# familab_pov_finished.net
KiCad netlist of a schematic drawn in EAGLE
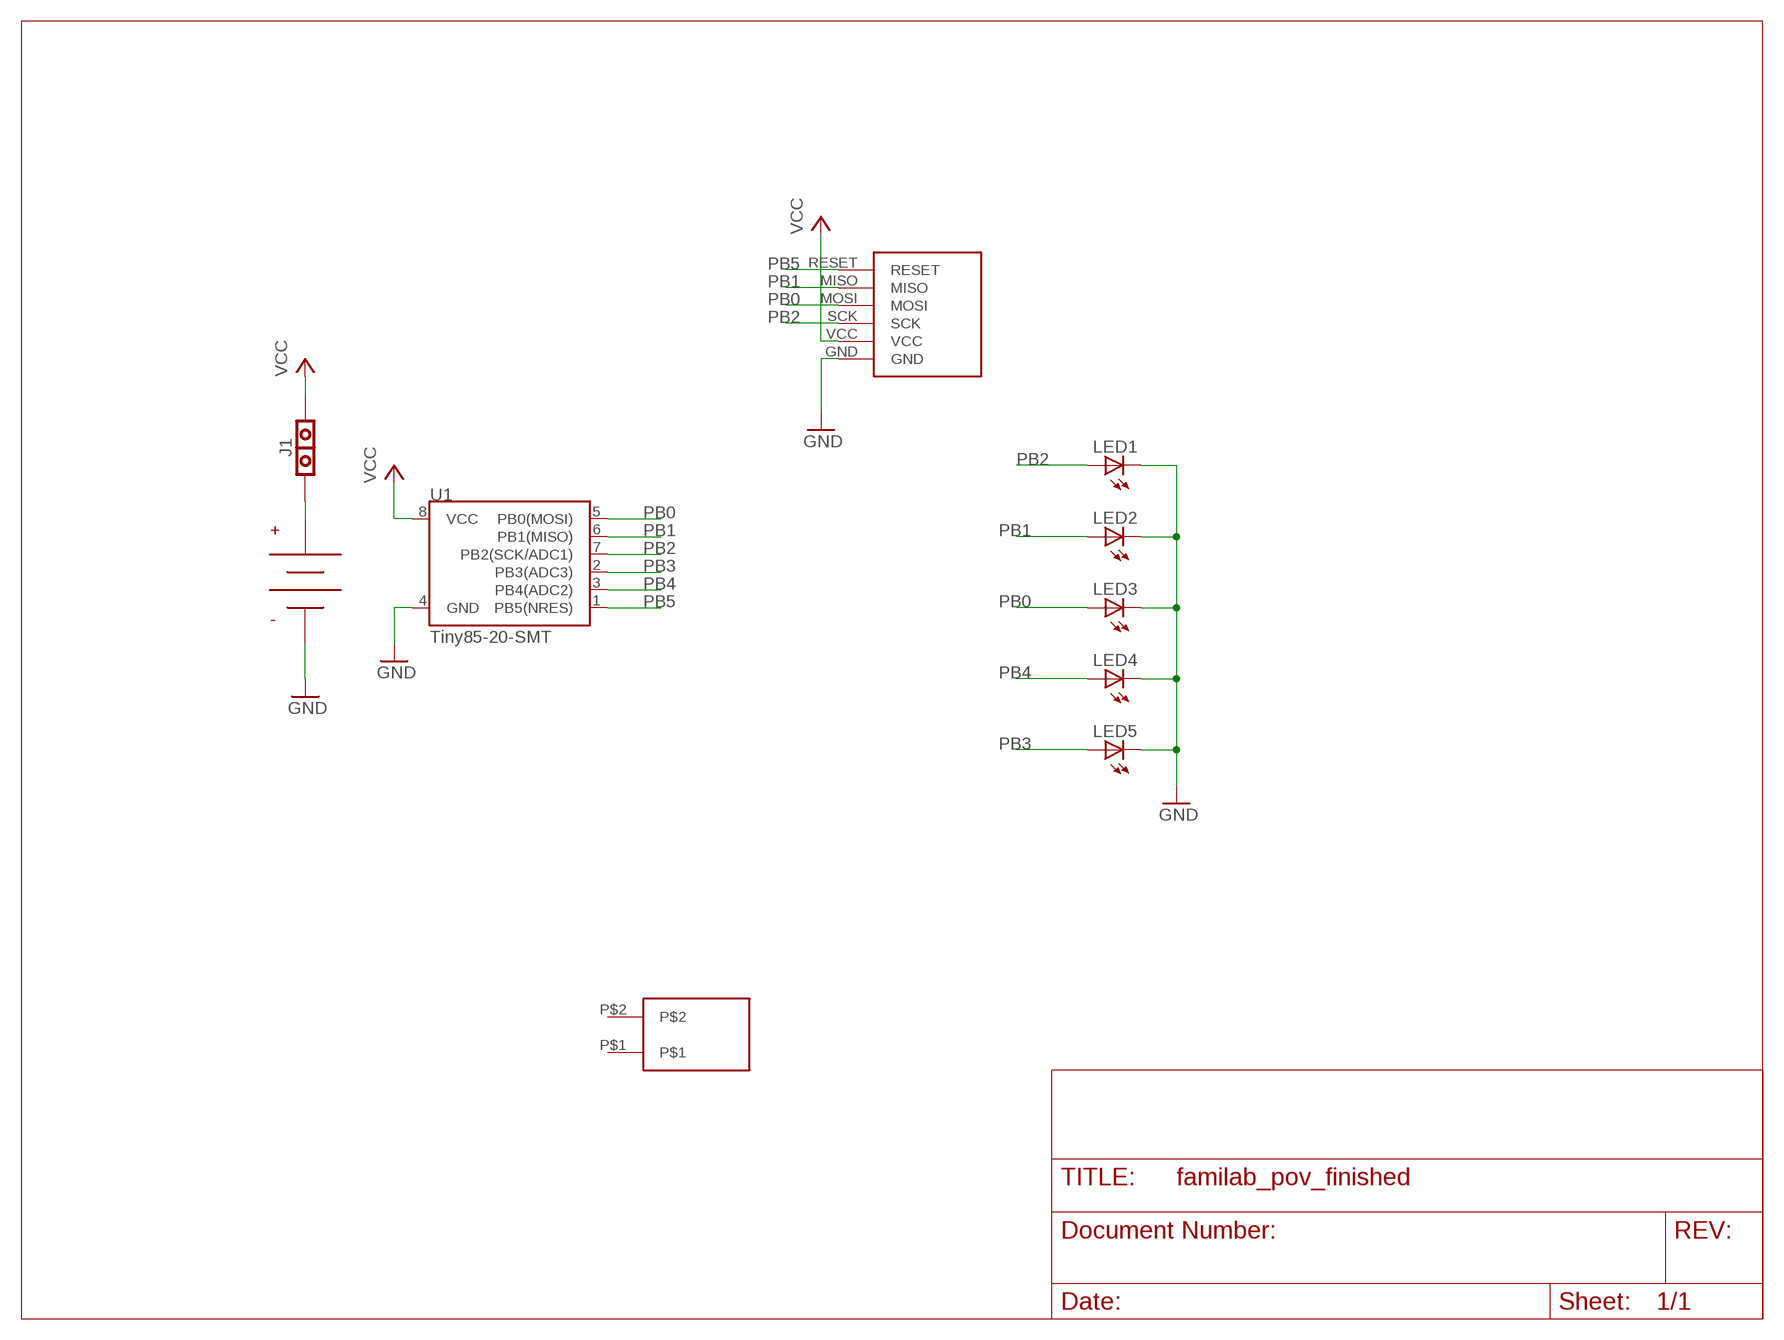
[diagram p0: schematic, sheet 1]

(export (version "E")
  (design (tool "Eeschema 10.0.6"))
  (components
    (comp (ref "J1")
      (value "JUMPERSIDE")
      (footprint "eagle-import:JUMPER_SMD_SIDE")
      (libsource (lib "eagle-import") (part "JUMPERSIDE"))
    )
    (comp (ref "LED1")
      (value "LEDLED_5MM_SMD_SIDE")
      (footprint "eagle-import:LED5MM_SMD_SIDE")
      (libsource (lib "eagle-import") (part "LEDLED_5MM_SMD_SIDE"))
    )
    (comp (ref "LED2")
      (value "LEDLED_5MM_SMD_SIDE")
      (footprint "eagle-import:LED5MM_SMD_SIDE")
      (libsource (lib "eagle-import") (part "LEDLED_5MM_SMD_SIDE"))
    )
    (comp (ref "LED3")
      (value "LEDLED_5MM_SMD_SIDE")
      (footprint "eagle-import:LED5MM_SMD_SIDE")
      (libsource (lib "eagle-import") (part "LEDLED_5MM_SMD_SIDE"))
    )
    (comp (ref "LED4")
      (value "LEDLED_5MM_SMD_SIDE")
      (footprint "eagle-import:LED5MM_SMD_SIDE")
      (libsource (lib "eagle-import") (part "LEDLED_5MM_SMD_SIDE"))
    )
    (comp (ref "LED5")
      (value "LEDLED_5MM_SMD_SIDE")
      (footprint "eagle-import:LED5MM_SMD_SIDE")
      (libsource (lib "eagle-import") (part "LEDLED_5MM_SMD_SIDE"))
    )
    (comp (ref "U$1")
      (value "CR2032_HOLDER")
      (footprint "eagle-import:CR2032_BC2032-F1")
      (libsource (lib "eagle-import") (part "CR2032_HOLDER"))
    )
    (comp (ref "U$2")
      (value "MOUNTING_PAD")
      (footprint "eagle-import:MOUNTING_PADS")
      (libsource (lib "eagle-import") (part "MOUNTING_PAD"))
    )
    (comp (ref "U$4")
      (value "ICSP_PROGRAM")
      (footprint "eagle-import:POV_ISP_CONNECTOR")
      (libsource (lib "eagle-import") (part "ICSP_PROGRAM"))
    )
    (comp (ref "U1")
      (value "Tiny85-20-SMT")
      (footprint "eagle-import:SO08-EIAJ")
      (libsource (lib "eagle-import") (part "ATTINY45TINY85-20-SMT"))
    )
  )
  (nets
    (net (code "1") (name "/PB0") (class "Default")
      (node (ref "LED3") (pin "ANODE") (pinfunction "A_ANODE") (pintype "passive"))
      (node (ref "U$4") (pin "MOSI") (pinfunction "MOSI_MOSI") (pintype "bidirectional"))
      (node (ref "U1") (pin "5") (pinfunction "PB0(MOSI)_5") (pintype "bidirectional"))
    )
    (net (code "2") (name "/PB1") (class "Default")
      (node (ref "LED2") (pin "ANODE") (pinfunction "A_ANODE") (pintype "passive"))
      (node (ref "U$4") (pin "MISO") (pinfunction "MISO_MISO") (pintype "bidirectional"))
      (node (ref "U1") (pin "6") (pinfunction "PB1(MISO)_6") (pintype "bidirectional"))
    )
    (net (code "3") (name "/PB2") (class "Default")
      (node (ref "LED1") (pin "ANODE") (pinfunction "A_ANODE") (pintype "passive"))
      (node (ref "U$4") (pin "SCK") (pinfunction "SCK_SCK") (pintype "bidirectional"))
      (node (ref "U1") (pin "7") (pinfunction "PB2(SCK/ADC1)_7") (pintype "bidirectional"))
    )
    (net (code "4") (name "/PB3") (class "Default")
      (node (ref "LED5") (pin "ANODE") (pinfunction "A_ANODE") (pintype "passive"))
      (node (ref "U1") (pin "2") (pinfunction "PB3(ADC3)_2") (pintype "bidirectional"))
    )
    (net (code "5") (name "/PB4") (class "Default")
      (node (ref "LED4") (pin "ANODE") (pinfunction "A_ANODE") (pintype "passive"))
      (node (ref "U1") (pin "3") (pinfunction "PB4(ADC2)_3") (pintype "bidirectional"))
    )
    (net (code "6") (name "/PB5") (class "Default")
      (node (ref "U$4") (pin "RESET") (pinfunction "RESET_RESET") (pintype "bidirectional"))
      (node (ref "U1") (pin "1") (pinfunction "PB5(NRES)_1") (pintype "bidirectional"))
    )
    (net (code "7") (name "GND") (class "Default")
      (node (ref "LED1") (pin "CATHODE") (pinfunction "C_CATHODE") (pintype "passive"))
      (node (ref "LED2") (pin "CATHODE") (pinfunction "C_CATHODE") (pintype "passive"))
      (node (ref "LED3") (pin "CATHODE") (pinfunction "C_CATHODE") (pintype "passive"))
      (node (ref "LED4") (pin "CATHODE") (pinfunction "C_CATHODE") (pintype "passive"))
      (node (ref "LED5") (pin "CATHODE") (pinfunction "C_CATHODE") (pintype "passive"))
      (node (ref "U$1") (pin "NEG") (pinfunction "NEG_NEG") (pintype "bidirectional"))
      (node (ref "U$4") (pin "GND") (pinfunction "GND_GND") (pintype "bidirectional"))
      (node (ref "U1") (pin "4") (pinfunction "GND_4") (pintype "bidirectional"))
    )
    (net (code "8") (name "Net-(J1-PadP$1)") (class "Default")
      (node (ref "J1") (pin "P$1") (pinfunction "P$1_P$1") (pintype "bidirectional"))
      (node (ref "U$1") (pin "POS") (pinfunction "POS_POS") (pintype "bidirectional"))
    )
    (net (code "9") (name "VCC") (class "Default")
      (node (ref "J1") (pin "P$2") (pinfunction "P$2_P$2") (pintype "bidirectional"))
      (node (ref "U$4") (pin "VCC") (pinfunction "VCC_VCC") (pintype "bidirectional"))
      (node (ref "U1") (pin "8") (pinfunction "VCC_8") (pintype "bidirectional"))
    )
    (net (code "10") (name "unconnected-(U$2-PadP$1)") (class "Default")
      (node (ref "U$2") (pin "P$1") (pinfunction "P$1_P$1") (pintype "bidirectional"))
    )
    (net (code "11") (name "unconnected-(U$2-PadP$2)") (class "Default")
      (node (ref "U$2") (pin "P$2") (pinfunction "P$2_P$2") (pintype "bidirectional"))
    )
  )
)
